# BMS_SERIAL.net
KiCad netlist of a schematic drawn in Altium Designer
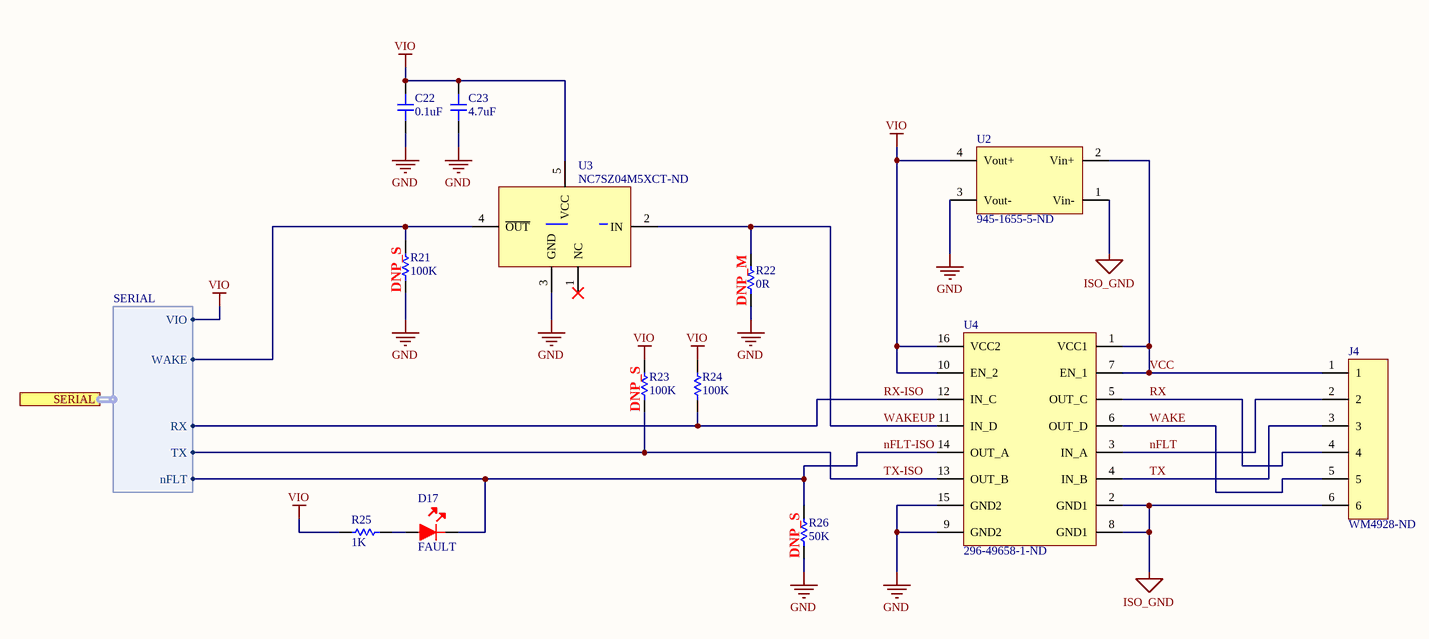
[diagram p0: BMS_SERIAL.SchDoc]

(export (version "E")
  (design (tool "Eeschema 10.0.6"))
  (components
    (comp (ref "C22")
      (value "0.1uF")
      (footprint "CAP-0805")
      (description "CAP CER 0.1UF 50V Y5V 0805")
      (fields
        (field (name "MANUFACTURER") "KEMET")
        (field (name "MANUFACTURER PART NUMBER") "C0805C104Z5VACTU")
      )
      (libsource (lib "Capacitors") (part "0805-0.1uF-50V"))
    )
    (comp (ref "C23")
      (value "4.7uF")
      (footprint "CAP-0805")
      (description "CAP CER 4.7UF 16V X5R 0805")
      (fields
        (field (name "MANUFACTURER") "KEMET")
        (field (name "MANUFACTURER PART NUMBER") "C0805C475K4PACTU")
      )
      (libsource (lib "Capacitors") (part "0805-4.7uF-16V"))
    )
    (comp (ref "D17")
      (value "FAULT")
      (footprint "LED-0603")
      (description "LED RED CLEAR 0603 SMD")
      (fields
        (field (name "MANUFACTURER") "Wurth Electronics")
        (field (name "MANUFACTURER PART NUMBER") "150060RS75000")
      )
      (libsource (lib "LEDs") (part "LED-Red"))
    )
    (comp (ref "J4")
      (value "WM4928-ND")
      (footprint "6PIN")
      (description "CONN HEADER R/A 6POS 2.54MM")
      (fields (field (name "MANUFACTURER") "Molex") (field (name "MANUFACTURER PART NUMBER") "70553-0040"))
      (libsource (lib "Connectors") (part "6PIN"))
    )
    (comp (ref "R21")
      (value "100K")
      (footprint "RES-0603")
      (description "RES 100K OHM 1% 1/10W 0603")
      (fields
        (field (name "MANUFACTURER") "Stackpole Electronics")
        (field (name "MANUFACTURER PART NUMBER") "RMCF0603FT100K")
      )
      (libsource (lib "Resistors") (part "0603-100KR"))
    )
    (comp (ref "R22")
      (value "0R")
      (footprint "RES-0603")
      (description "RES SMD 0 OHM JUMPER 1/10W 0603")
      (fields
        (field (name "MANUFACTURER") "Yageo")
        (field (name "MANUFACTURER PART NUMBER") "RC0603JR-070RL")
      )
      (libsource (lib "Resistors") (part "0603-0R"))
    )
    (comp (ref "R23")
      (value "100K")
      (footprint "RES-0603")
      (description "RES 100K OHM 1% 1/10W 0603")
      (fields
        (field (name "MANUFACTURER") "Stackpole Electronics")
        (field (name "MANUFACTURER PART NUMBER") "RMCF0603FT100K")
      )
      (libsource (lib "Resistors") (part "0603-100KR"))
    )
    (comp (ref "R24")
      (value "100K")
      (footprint "RES-0603")
      (description "RES 100K OHM 1% 1/10W 0603")
      (fields
        (field (name "MANUFACTURER") "Stackpole Electronics")
        (field (name "MANUFACTURER PART NUMBER") "RMCF0603FT100K")
      )
      (libsource (lib "Resistors") (part "0603-100KR"))
    )
    (comp (ref "R25")
      (value "1K")
      (footprint "RES-0603")
      (description "RES SMD 1K OHM 1% 1/10W 0603")
      (fields
        (field (name "MANUFACTURER") "Vishay Dale")
        (field (name "MANUFACTURER PART NUMBER") "CRCW06031K00FKEA")
      )
      (libsource (lib "Resistors") (part "0603-1KR"))
    )
    (comp (ref "R26")
      (value "50K")
      (footprint "RES-0603")
      (description "RES SMD 49.9K OHM 1% 1/10W 0603")
      (fields
        (field (name "MANUFACTURER") "Yageo")
        (field (name "MANUFACTURER PART NUMBER") "RC0603FR-0749K9L")
      )
      (libsource (lib "Resistors") (part "0603-50KR"))
    )
    (comp (ref "U2")
      (value "945-1655-5-ND")
      (footprint "ROE5050")
      (description "DC DC CONVERTER 5V 1W")
      (fields (field (name "MANUFACTURER") "Recom") (field (name "MANUFACTURER PART NUMBER") "ROE-0505S"))
      (libsource (lib "Power") (part "DCDC5V-5V"))
    )
    (comp (ref "U3")
      (value "NC7SZ04M5XCT-ND")
      (footprint "SOT-23-5")
      (description "IC INVERTER 1CH 1-INP SOT23-5")
      (fields
        (field (name "MANUFACTURER") "ON Semiconductor / Fairchild")
        (field (name "MANUFACTURER PART NUMBER") "NC7SZ04M5X")
      )
      (libsource (lib "Logic") (part "Invert-NC7SZ04M5X"))
    )
    (comp (ref "U4")
      (value "296-49658-1-ND")
      (footprint "16-SSOP")
      (description "DGTL ISO 2500VRMS 4CH GP 16SSOP")
      (fields
        (field (name "MANUFACTURER") "Texas Instruments")
        (field (name "MANUFACTURER PART NUMBER") "ISO7742DBQR")
      )
      (libsource (lib "ICs") (part "4channel-ISO"))
    )
  )
  (nets
    (net (code "2") (name "/RX") (class "Default")
      (node (ref "J4") (pin "4") (pinfunction "4_4") (pintype "passive"))
      (node (ref "U4") (pin "5") (pinfunction "OUT_C_5") (pintype "passive"))
    )
    (net (code "3") (name "/RX-ISO") (class "Default")
      (node (ref "R24") (pin "1") (pinfunction "1_1") (pintype "passive"))
      (node (ref "U4") (pin "12") (pinfunction "IN_C_12") (pintype "passive"))
    )
    (net (code "4") (name "/TX") (class "Default")
      (node (ref "J4") (pin "3") (pinfunction "3_3") (pintype "passive"))
      (node (ref "U4") (pin "4") (pinfunction "IN_B_4") (pintype "passive"))
    )
    (net (code "5") (name "/TX-ISO") (class "Default")
      (node (ref "R23") (pin "1") (pinfunction "1_1") (pintype "passive"))
      (node (ref "U4") (pin "13") (pinfunction "OUT_B_13") (pintype "passive"))
    )
    (net (code "6") (name "/VCC") (class "Default")
      (node (ref "J4") (pin "1") (pinfunction "1_1") (pintype "passive"))
      (node (ref "U2") (pin "2") (pinfunction "Vin+_2") (pintype "passive"))
      (node (ref "U4") (pin "1") (pinfunction "VCC1_1") (pintype "passive"))
      (node (ref "U4") (pin "7") (pinfunction "EN_1_7") (pintype "passive"))
    )
    (net (code "7") (name "/WAKE") (class "Default")
      (node (ref "J4") (pin "5") (pinfunction "5_5") (pintype "passive"))
      (node (ref "U4") (pin "6") (pinfunction "OUT_D_6") (pintype "passive"))
    )
    (net (code "8") (name "/WAKEUP") (class "Default")
      (node (ref "R22") (pin "2") (pinfunction "2_2") (pintype "passive"))
      (node (ref "U3") (pin "2") (pinfunction "IN_2") (pintype "passive"))
      (node (ref "U4") (pin "11") (pinfunction "IN_D_11") (pintype "passive"))
    )
    (net (code "9") (name "/nFLT") (class "Default")
      (node (ref "J4") (pin "2") (pinfunction "2_2") (pintype "passive"))
      (node (ref "U4") (pin "3") (pinfunction "IN_A_3") (pintype "passive"))
    )
    (net (code "10") (name "/nFLT-ISO") (class "Default")
      (node (ref "D17") (pin "2") (pinfunction "2_2") (pintype "passive"))
      (node (ref "R26") (pin "2") (pinfunction "2_2") (pintype "passive"))
      (node (ref "U4") (pin "14") (pinfunction "OUT_A_14") (pintype "passive"))
    )
    (net (code "12") (name "GND") (class "Default")
      (node (ref "C22") (pin "1") (pinfunction "1_1") (pintype "passive"))
      (node (ref "C23") (pin "1") (pinfunction "1_1") (pintype "passive"))
      (node (ref "R21") (pin "1") (pinfunction "1_1") (pintype "passive"))
      (node (ref "R22") (pin "1") (pinfunction "1_1") (pintype "passive"))
      (node (ref "R26") (pin "1") (pinfunction "1_1") (pintype "passive"))
      (node (ref "U2") (pin "3") (pinfunction "Vout-_3") (pintype "passive"))
      (node (ref "U3") (pin "3") (pinfunction "GND_3") (pintype "passive"))
      (node (ref "U4") (pin "15") (pinfunction "GND2_15") (pintype "passive"))
      (node (ref "U4") (pin "9") (pinfunction "GND2_9") (pintype "passive"))
    )
    (net (code "13") (name "ISO_GND") (class "Default")
      (node (ref "J4") (pin "6") (pinfunction "6_6") (pintype "passive"))
      (node (ref "U2") (pin "1") (pinfunction "Vin-_1") (pintype "passive"))
      (node (ref "U4") (pin "2") (pinfunction "GND1_2") (pintype "passive"))
      (node (ref "U4") (pin "8") (pinfunction "GND1_8") (pintype "passive"))
    )
    (net (code "14") (name "Net-(D17-Pad1)") (class "Default")
      (node (ref "D17") (pin "1") (pinfunction "1_1") (pintype "passive"))
      (node (ref "R25") (pin "1") (pinfunction "1_1") (pintype "passive"))
    )
    (net (code "15") (name "Net-(U3-~{OUT})") (class "Default")
      (node (ref "R21") (pin "2") (pinfunction "2_2") (pintype "passive"))
      (node (ref "U3") (pin "4") (pinfunction "~{OUT}_4") (pintype "passive"))
    )
    (net (code "16") (name "VIO") (class "Default")
      (node (ref "C22") (pin "2") (pinfunction "2_2") (pintype "passive"))
      (node (ref "C23") (pin "2") (pinfunction "2_2") (pintype "passive"))
      (node (ref "R23") (pin "2") (pinfunction "2_2") (pintype "passive"))
      (node (ref "R24") (pin "2") (pinfunction "2_2") (pintype "passive"))
      (node (ref "R25") (pin "2") (pinfunction "2_2") (pintype "passive"))
      (node (ref "U2") (pin "4") (pinfunction "Vout+_4") (pintype "passive"))
      (node (ref "U3") (pin "5") (pinfunction "VCC_5") (pintype "passive"))
      (node (ref "U4") (pin "10") (pinfunction "EN_2_10") (pintype "passive"))
      (node (ref "U4") (pin "16") (pinfunction "VCC2_16") (pintype "passive"))
    )
    (net (code "17") (name "unconnected-(U3-NC-Pad1)") (class "Default")
      (node (ref "U3") (pin "1") (pinfunction "NC_1") (pintype "passive+no_connect"))
    )
  )
)
